# Sheet1.net
KiCad netlist of a schematic drawn in Altium Designer
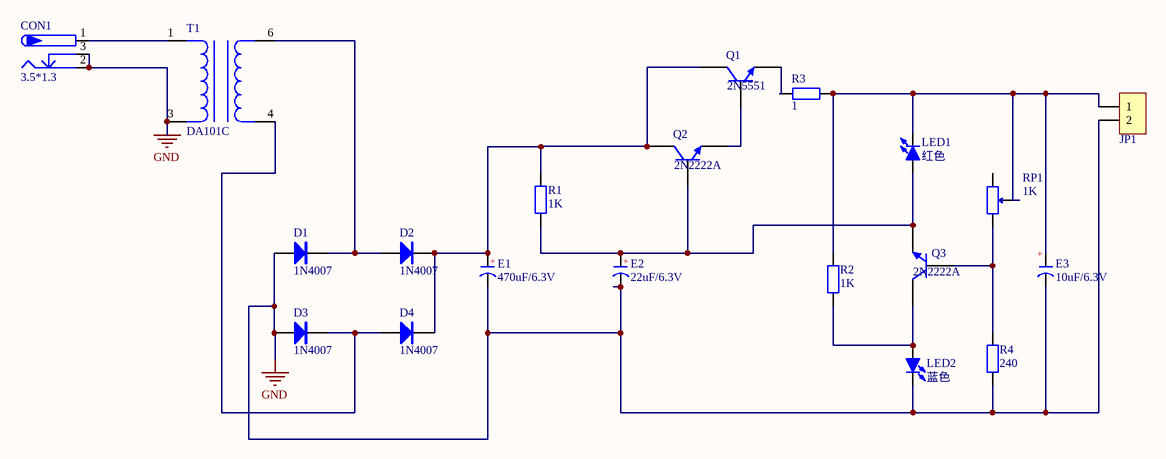
[diagram p0: Sheet1.SchDoc]

(export (version "E")
  (design (tool "Eeschema 10.0.6"))
  (components
    (comp (ref "CON1")
      (value "3.5*1.3")
      (footprint "DC-005")
      (description "低压电源接口")
      (fields (field (name "版权归属") "源创客"))
      (libsource (lib "接口类") (part "P-DC"))
    )
    (comp (ref "D1")
      (value "1N4007")
      (footprint "DO-41")
      (description "整流二极管")
      (fields (field (name "版权归属") "源创客"))
      (libsource (lib "8.1   - 二极管-整流桥") (part "1N4007"))
    )
    (comp (ref "D2")
      (value "1N4007")
      (footprint "DO-41")
      (description "整流二极管")
      (fields (field (name "版权归属") "源创客"))
      (libsource (lib "8.1   - 二极管-整流桥") (part "1N4007"))
    )
    (comp (ref "D3")
      (value "1N4007")
      (footprint "DO-41")
      (description "整流二极管")
      (fields (field (name "版权归属") "源创客"))
      (libsource (lib "8.1   - 二极管-整流桥") (part "1N4007"))
    )
    (comp (ref "D4")
      (value "1N4007")
      (footprint "DO-41")
      (description "整流二极管")
      (fields (field (name "版权归属") "源创客"))
      (libsource (lib "8.1   - 二极管-整流桥") (part "1N4007"))
    )
    (comp (ref "E1")
      (value "470uF/6.3V")
      (footprint "CS 2.5*6.3*11 - C")
      (description "直插固态电容")
      (fields (field (name "版权归属") "源创客"))
      (libsource (lib "") (part "C-CS_1"))
    )
    (comp (ref "E2")
      (value "22uF/6.3V")
      (footprint "CS 2.0*5*8 - C")
      (description "直插固态电容")
      (fields (field (name "版权归属") "源创客"))
      (libsource (lib "") (part "C-CS_1"))
    )
    (comp (ref "E3")
      (value "10uF/6.3V")
      (footprint "CS 2.0*5*8 - C")
      (description "直插固态电容")
      (fields (field (name "版权归属") "源创客"))
      (libsource (lib "3.1   - 电阻-电容-电感") (part "C-CS"))
    )
    (comp (ref "JP1")
      (value "HDR-1X2")
      (footprint "VH3.96-LI-2P")
      (description "2P接插件")
      (fields (field (name "版权归属") "源创客"))
      (libsource (lib "4.8   - 接插件-脚距3.96") (part "Header 2"))
    )
    (comp (ref "LED1")
      (value "红色")
      (footprint "LED 0805R")
      (description "贴片LED")
      (fields (field (name "版权归属") "源创客"))
      (libsource (lib "9.1   - LED") (part "LED-SMD"))
    )
    (comp (ref "LED2")
      (value "蓝色")
      (footprint "LED 0805B")
      (description "贴片LED")
      (fields (field (name "版权归属") "源创客"))
      (libsource (lib "9.1   - LED") (part "LED-SMD"))
    )
    (comp (ref "Q1")
      (value "2N5551")
      (footprint "TO-92A")
      (description "NPN General Purpose Amplifier")
      (fields (field (name "PUBLISHER") "Altium Limited"))
      (libsource (lib "Miscellaneous Devices") (part "2N3904"))
    )
    (comp (ref "Q2")
      (value "2N2222A")
      (footprint "TO-92A")
      (description "NPN General Purpose Amplifier")
      (fields (field (name "PUBLISHER") "Altium Limited"))
      (libsource (lib "Miscellaneous Devices") (part "2N3904"))
    )
    (comp (ref "Q3")
      (value "2N2222A")
      (footprint "TO-92A")
      (description "NPN General Purpose Amplifier")
      (fields (field (name "PUBLISHER") "Altium Limited"))
      (libsource (lib "Miscellaneous Devices") (part "2N3904"))
    )
    (comp (ref "R1")
      (value "1K")
      (footprint "R 0805_L")
      (description "贴片电阻")
      (fields (field (name "版权归属") "源创客"))
      (libsource (lib "3.1   - 电阻-电容-电感") (part "R"))
    )
    (comp (ref "R2")
      (value "1K")
      (footprint "R 0805_L")
      (description "贴片电阻")
      (fields (field (name "版权归属") "源创客"))
      (libsource (lib "3.1   - 电阻-电容-电感") (part "R"))
    )
    (comp (ref "R3")
      (value "1")
      (footprint "R 0805_L")
      (description "贴片电阻")
      (fields (field (name "版权归属") "源创客"))
      (libsource (lib "3.1   - 电阻-电容-电感") (part "R"))
    )
    (comp (ref "R4")
      (value "240")
      (footprint "R 0805_L")
      (description "贴片电阻")
      (fields (field (name "版权归属") "源创客"))
      (libsource (lib "3.1   - 电阻-电容-电感") (part "R"))
    )
    (comp (ref "RP1")
      (value "1K")
      (footprint "3296W")
      (description "单联电位器")
      (libsource (lib "0.1 - 电阻-电容-电感-电位器") (part "RP"))
    )
    (comp (ref "T1")
      (value "DA101C")
      (footprint "DA10XC")
      (description "数字隔离变压器")
      (fields (field (name "版权归属") "源创客"))
      (libsource (lib "12.1 - 变压器") (part "DA10XC"))
    )
  )
  (nets
    (net (code "1") (name "GND") (class "Default")
      (node (ref "CON1") (pin "2") (pintype "power_in"))
      (node (ref "CON1") (pin "3") (pintype "power_in"))
      (node (ref "D1") (pin "1") (pinfunction "A_1") (pintype "passive"))
      (node (ref "D3") (pin "1") (pinfunction "A_1") (pintype "passive"))
      (node (ref "E1") (pin "2") (pinfunction "K_2") (pintype "passive"))
      (node (ref "E2") (pin "2") (pinfunction "K_2") (pintype "passive"))
      (node (ref "E3") (pin "2") (pinfunction "K_2") (pintype "passive"))
      (node (ref "JP1") (pin "2") (pinfunction "2_2") (pintype "passive"))
      (node (ref "LED2") (pin "2") (pinfunction "K_2") (pintype "passive"))
      (node (ref "R4") (pin "1") (pinfunction "1_1") (pintype "passive"))
      (node (ref "T1") (pin "3") (pinfunction "3_3") (pintype "passive"))
    )
    (net (code "2") (name "Net-(CON1-Pad1)") (class "Default")
      (node (ref "CON1") (pin "1") (pintype "power_in"))
      (node (ref "T1") (pin "1") (pinfunction "1_1") (pintype "passive"))
    )
    (net (code "3") (name "Net-(D1-K)") (class "Default")
      (node (ref "D1") (pin "2") (pinfunction "K_2") (pintype "passive"))
      (node (ref "D2") (pin "1") (pinfunction "A_1") (pintype "passive"))
      (node (ref "T1") (pin "6") (pinfunction "6_6") (pintype "passive"))
    )
    (net (code "4") (name "Net-(D2-K)") (class "Default")
      (node (ref "D2") (pin "2") (pinfunction "K_2") (pintype "passive"))
      (node (ref "D4") (pin "2") (pinfunction "K_2") (pintype "passive"))
      (node (ref "E1") (pin "1") (pinfunction "A_1") (pintype "passive"))
      (node (ref "Q1") (pin "3") (pinfunction "C_3") (pintype "passive"))
      (node (ref "Q2") (pin "3") (pinfunction "C_3") (pintype "passive"))
      (node (ref "R1") (pin "2") (pinfunction "2_2") (pintype "passive"))
    )
    (net (code "5") (name "Net-(D3-K)") (class "Default")
      (node (ref "D3") (pin "2") (pinfunction "K_2") (pintype "passive"))
      (node (ref "D4") (pin "1") (pinfunction "A_1") (pintype "passive"))
      (node (ref "T1") (pin "4") (pinfunction "4_4") (pintype "passive"))
    )
    (net (code "6") (name "Net-(E2-A)") (class "Default")
      (node (ref "E2") (pin "1") (pinfunction "A_1") (pintype "passive"))
      (node (ref "LED1") (pin "1") (pinfunction "A_1") (pintype "passive"))
      (node (ref "Q2") (pin "2") (pinfunction "B_2") (pintype "passive"))
      (node (ref "Q3") (pin "1") (pinfunction "E_1") (pintype "passive"))
      (node (ref "R1") (pin "1") (pinfunction "1_1") (pintype "passive"))
    )
    (net (code "7") (name "Net-(E3-A)") (class "Default")
      (node (ref "E3") (pin "1") (pinfunction "A_1") (pintype "passive"))
      (node (ref "JP1") (pin "1") (pinfunction "1_1") (pintype "passive"))
      (node (ref "LED1") (pin "2") (pinfunction "K_2") (pintype "passive"))
      (node (ref "R2") (pin "2") (pinfunction "2_2") (pintype "passive"))
      (node (ref "R3") (pin "2") (pinfunction "2_2") (pintype "passive"))
      (node (ref "RP1") (pin "2") (pinfunction "2_2") (pintype "passive"))
    )
    (net (code "8") (name "Net-(LED2-A)") (class "Default")
      (node (ref "LED2") (pin "1") (pinfunction "A_1") (pintype "passive"))
      (node (ref "Q3") (pin "3") (pinfunction "C_3") (pintype "passive"))
      (node (ref "R2") (pin "1") (pinfunction "1_1") (pintype "passive"))
    )
    (net (code "9") (name "Net-(Q1-B)") (class "Default")
      (node (ref "Q1") (pin "2") (pinfunction "B_2") (pintype "passive"))
      (node (ref "Q2") (pin "1") (pinfunction "E_1") (pintype "passive"))
    )
    (net (code "10") (name "Net-(Q1-E)") (class "Default")
      (node (ref "Q1") (pin "1") (pinfunction "E_1") (pintype "passive"))
      (node (ref "R3") (pin "1") (pinfunction "1_1") (pintype "passive"))
    )
    (net (code "11") (name "Net-(Q3-B)") (class "Default")
      (node (ref "Q3") (pin "2") (pinfunction "B_2") (pintype "passive"))
      (node (ref "R4") (pin "2") (pinfunction "2_2") (pintype "passive"))
      (node (ref "RP1") (pin "3") (pinfunction "3_3") (pintype "passive"))
    )
    (net (code "12") (name "unconnected-(RP1-Pad1)") (class "Default")
      (node (ref "RP1") (pin "1") (pinfunction "1_1") (pintype "passive"))
    )
  )
)
